# LMX2592.net
KiCad netlist of a schematic drawn in Altium Designer
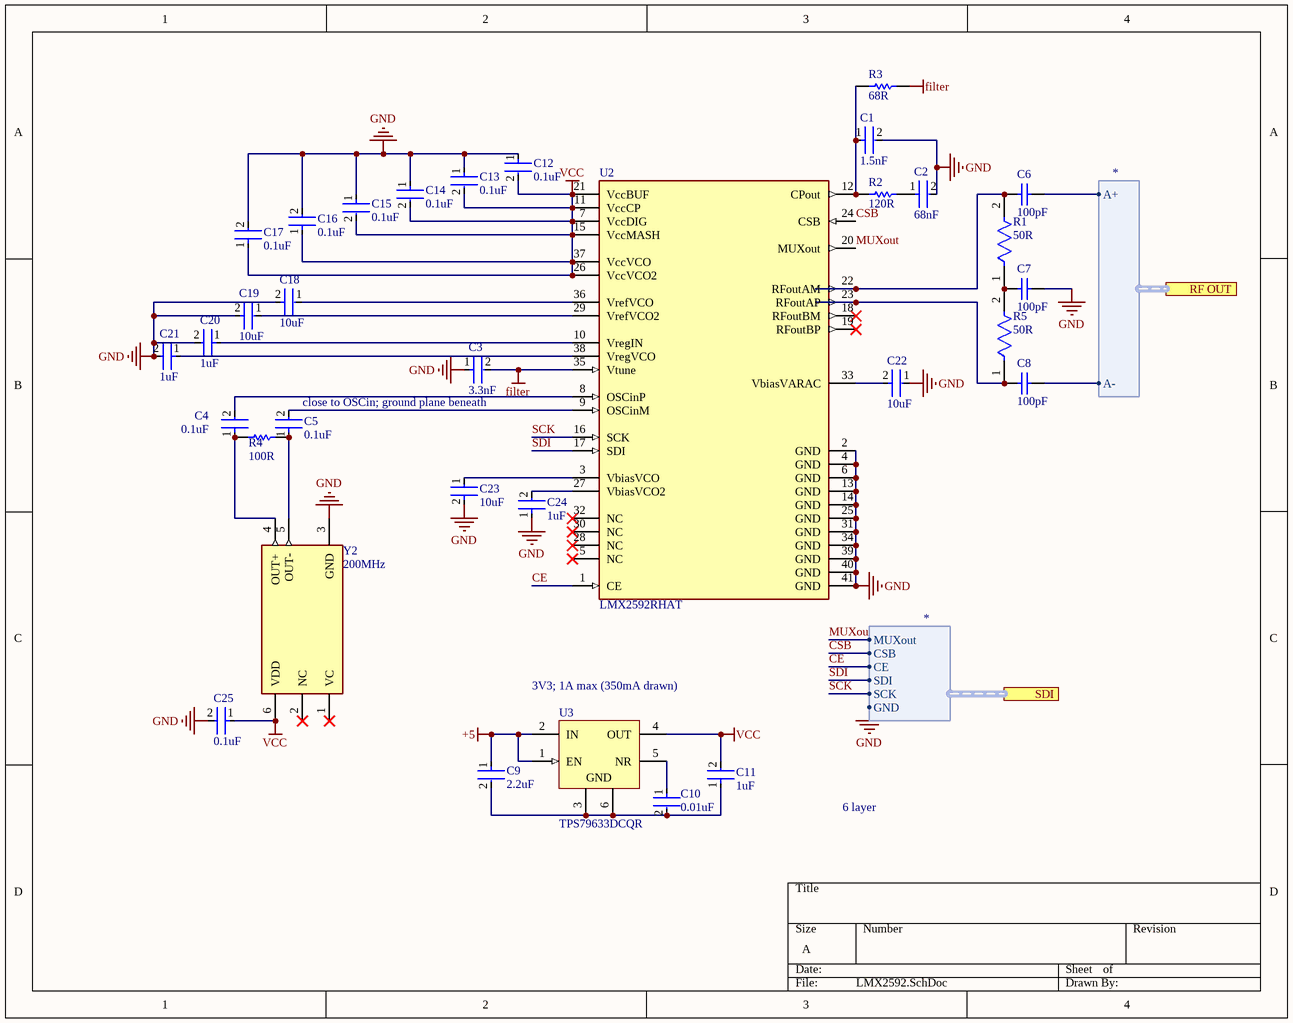
[diagram p0: LMX2592.SchDoc]

(export (version "E")
  (design (tool "Eeschema 10.0.6"))
  (components
    (comp (ref "C1")
      (value "1.5nF")
      (footprint "FP-GRM188-0_1-e0_2_0_5-IPC_B")
      (description "Chip Multilayer Ceramic Capacitors for General Purpose, 0603, 1500pF, C0G, 30ppm/°C, 5%, 50V")
      (fields (field (name "TOLERANCE") "5%") (field (name "VOLTAGE") "50V"))
      (libsource (lib "Altium Content Vault") (part "11868f565c42a9108669ba33697ecf6"))
    )
    (comp (ref "C2")
      (value "68nF")
      (footprint "FP-GRM319-0_15-MFG")
      (description "Chip Multilayer Ceramic Capacitors for General Purpose, 1206, 68000pF, C0G, 30ppm/°C, 5%, 50V")
      (libsource (lib "Altium Content Vault") (part "b4654b650e69147ec39a6b967a45e02"))
    )
    (comp (ref "C3")
      (value "3.3nF")
      (footprint "FP-GCM188-0_1-MFG")
      (description "Ceramic Capacitor for Automotive 3.3nF  ±1% 50VDC C0G 0603 Paper T/R")
      (libsource (lib "Altium Content Vault") (part "02cd4be3c70576c341d710602a673aa"))
    )
    (comp (ref "C4")
      (value "0.1uF")
      (footprint "FP-C0603C-CF-MFG")
      (description "CAP CER 0.1UF 50V X7R 0603")
      (fields (field (name "TOLERANCE") "0.1") (field (name "MANUFACTURER") "KEMET"))
      (libsource (lib "Altium Content Vault") (part "b4654b650e69147ec39a6b967a45e02"))
    )
    (comp (ref "C5")
      (value "0.1uF")
      (footprint "FP-C0603C-CF-MFG")
      (description "CAP CER 0.1UF 50V X7R 0603")
      (fields (field (name "TOLERANCE") "0.1") (field (name "MANUFACTURER") "KEMET"))
      (libsource (lib "Altium Content Vault") (part "b4654b650e69147ec39a6b967a45e02"))
    )
    (comp (ref "C6")
      (value "100pF")
      (footprint "CAPC1608X90X35NL10T15")
      (fields (field (name "PART NUMBER") "GRM1885C1H101JA01D") (field (name "MANUFACTURER") "Murata"))
      (libsource (lib "Altium Content Vault") (part "CAP"))
    )
    (comp (ref "C7")
      (value "100pF")
      (footprint "CAPC1608X90X35NL10T15")
      (fields (field (name "PART NUMBER") "GRM1885C1H101JA01D") (field (name "MANUFACTURER") "Murata"))
      (libsource (lib "Altium Content Vault") (part "CAP"))
    )
    (comp (ref "C8")
      (value "100pF")
      (footprint "CAPC1608X90X35NL10T15")
      (fields (field (name "PART NUMBER") "GRM1885C1H101JA01D") (field (name "MANUFACTURER") "Murata"))
      (libsource (lib "Altium Content Vault") (part "CAP"))
    )
    (comp (ref "C9")
      (value "2.2uF")
      (footprint "FP-GRM188-0_1-e0_2_0_5-MFG")
      (description "Chip Multilayer Ceramic Capacitors for General Purpose, 0603, 2.2uF, X7R, 15%, 10%, 10V")
      (fields (field (name "VOLTAGE") "10V") (field (name "TOLERANCE") "10%"))
      (libsource (lib "Altium Content Vault") (part "11868f565c42a9108669ba33697ecf6"))
    )
    (comp (ref "C10")
      (value "0.01uF")
      (footprint "FP-C0603C-CF-MFG")
      (description "CAP CER 10000PF 50V X7R 0603")
      (fields
        (field (name "MANUFACTURER") "KEMET")
        (field (name "OCTOPART") "https://octopart.com/c0603c103k5ractu-kemet-133094")
      )
      (libsource (lib "Altium Content Vault") (part "b4654b650e69147ec39a6b967a45e02"))
    )
    (comp (ref "C11")
      (value "1uF")
      (footprint "FP-0603-L_1_6_0_15-W_0_8-IPC_C")
      (description "Ceramic Capacitor General Use 1uF ±10% 50V X7R 0603")
      (fields (field (name "TOLERANCE") "10%"))
      (libsource (lib "Altium Content Vault") (part "11868f565c42a9108669ba33697ecf6"))
    )
    (comp (ref "C12")
      (value "0.1uF")
      (footprint "FP-C0603C-CF-MFG")
      (description "CAP CER 0.1UF 50V X7R 0603")
      (fields (field (name "TOLERANCE") "0.1") (field (name "MANUFACTURER") "KEMET"))
      (libsource (lib "Altium Content Vault") (part "b4654b650e69147ec39a6b967a45e02"))
    )
    (comp (ref "C13")
      (value "0.1uF")
      (footprint "FP-C0603C-CF-MFG")
      (description "CAP CER 0.1UF 50V X7R 0603")
      (fields (field (name "TOLERANCE") "0.1") (field (name "MANUFACTURER") "KEMET"))
      (libsource (lib "Altium Content Vault") (part "b4654b650e69147ec39a6b967a45e02"))
    )
    (comp (ref "C14")
      (value "0.1uF")
      (footprint "FP-C0603C-CF-MFG")
      (description "CAP CER 0.1UF 50V X7R 0603")
      (fields (field (name "TOLERANCE") "0.1") (field (name "MANUFACTURER") "KEMET"))
      (libsource (lib "Altium Content Vault") (part "b4654b650e69147ec39a6b967a45e02"))
    )
    (comp (ref "C15")
      (value "0.1uF")
      (footprint "FP-C0603C-CF-MFG")
      (description "CAP CER 0.1UF 50V X7R 0603")
      (fields (field (name "TOLERANCE") "0.1") (field (name "MANUFACTURER") "KEMET"))
      (libsource (lib "Altium Content Vault") (part "b4654b650e69147ec39a6b967a45e02"))
    )
    (comp (ref "C16")
      (value "0.1uF")
      (footprint "FP-C0603C-CF-MFG")
      (description "CAP CER 0.1UF 50V X7R 0603")
      (fields (field (name "TOLERANCE") "0.1") (field (name "MANUFACTURER") "KEMET"))
      (libsource (lib "Altium Content Vault") (part "b4654b650e69147ec39a6b967a45e02"))
    )
    (comp (ref "C17")
      (value "0.1uF")
      (footprint "FP-C0603C-CF-MFG")
      (description "CAP CER 0.1UF 50V X7R 0603")
      (fields (field (name "TOLERANCE") "0.1") (field (name "MANUFACTURER") "KEMET"))
      (libsource (lib "Altium Content Vault") (part "b4654b650e69147ec39a6b967a45e02"))
    )
    (comp (ref "C18")
      (value "10uF")
      (footprint "FP-CL21B106KOQNNNE-MFG")
      (description "CAP CER 10UF 16V X7R 0805")
      (fields
        (field (name "MANUFACTURER PART NUMBER") "CL21B106KOQNNNE")
        (field (name "OCTOPART") "https://octopart.com/cl21b106koqnnne-samsung-19832289")
      )
      (libsource (lib "Altium Content Vault") (part "236180d848d6139a670b325ea6854c9"))
    )
    (comp (ref "C19")
      (value "10uF")
      (footprint "FP-CL21B106KOQNNNE-MFG")
      (description "CAP CER 10UF 16V X7R 0805")
      (fields
        (field (name "MANUFACTURER PART NUMBER") "CL21B106KOQNNNE")
        (field (name "OCTOPART") "https://octopart.com/cl21b106koqnnne-samsung-19832289")
      )
      (libsource (lib "Altium Content Vault") (part "236180d848d6139a670b325ea6854c9"))
    )
    (comp (ref "C20")
      (value "1uF")
      (footprint "FP-0603-L_1_6_0_15-W_0_8-IPC_C")
      (description "Ceramic Capacitor General Use 1uF ±10% 50V X7R 0603")
      (fields (field (name "TOLERANCE") "10%"))
      (libsource (lib "Altium Content Vault") (part "11868f565c42a9108669ba33697ecf6"))
    )
    (comp (ref "C21")
      (value "1uF")
      (footprint "FP-0603-L_1_6_0_15-W_0_8-IPC_C")
      (description "Ceramic Capacitor General Use 1uF ±10% 50V X7R 0603")
      (fields (field (name "TOLERANCE") "10%"))
      (libsource (lib "Altium Content Vault") (part "11868f565c42a9108669ba33697ecf6"))
    )
    (comp (ref "C22")
      (value "10uF")
      (footprint "FP-CL21B106KOQNNNE-MFG")
      (description "CAP CER 10UF 16V X7R 0805")
      (fields
        (field (name "MANUFACTURER PART NUMBER") "CL21B106KOQNNNE")
        (field (name "OCTOPART") "https://octopart.com/cl21b106koqnnne-samsung-19832289")
      )
      (libsource (lib "Altium Content Vault") (part "236180d848d6139a670b325ea6854c9"))
    )
    (comp (ref "C23")
      (value "10uF")
      (footprint "FP-CL21B106KOQNNNE-MFG")
      (description "CAP CER 10UF 16V X7R 0805")
      (fields
        (field (name "MANUFACTURER PART NUMBER") "CL21B106KOQNNNE")
        (field (name "OCTOPART") "https://octopart.com/cl21b106koqnnne-samsung-19832289")
      )
      (libsource (lib "Altium Content Vault") (part "236180d848d6139a670b325ea6854c9"))
    )
    (comp (ref "C24")
      (value "1uF")
      (footprint "FP-0603-L_1_6_0_15-W_0_8-IPC_C")
      (description "Ceramic Capacitor General Use 1uF ±10% 50V X7R 0603")
      (fields (field (name "TOLERANCE") "10%"))
      (libsource (lib "Altium Content Vault") (part "11868f565c42a9108669ba33697ecf6"))
    )
    (comp (ref "C25")
      (value "0.1uF")
      (footprint "FP-C0603C-CF-MFG")
      (description "CAP CER 0.1UF 50V X7R 0603")
      (fields (field (name "TOLERANCE") "0.1") (field (name "MANUFACTURER") "KEMET"))
      (libsource (lib "Altium Content Vault") (part "b4654b650e69147ec39a6b967a45e02"))
    )
    (comp (ref "R1")
      (value "50R")
      (footprint "FP-CRCW0603-e3-MFG")
      (description "RES Thick Film, 50Ω, 1%, 0.1W, 100ppm/°C, 0603")
      (fields (field (name "TOLERANCE") "1%"))
      (libsource (lib "Altium Content Vault") (part "1029c3af85768c4190bb7ad29bc67b5"))
    )
    (comp (ref "R2")
      (value "120R")
      (footprint "RESC1608X55X25NL10T15")
      (description "Chip Resistor, 120 Ohm, +/- 1%, 100 mW, -55 to 155 degC, 0603 (1608 Metric), RoHS, Tape and Reel")
      (libsource (lib "Altium Content Vault") (part "RES-2"))
    )
    (comp (ref "R3")
      (value "68R")
      (footprint "RESC1608X55X30ML15T15")
      (fields (field (name "PART NUMBER") "ERJ-3GEYJ680V") (field (name "MANUFACTURER") "Panasonic"))
      (libsource (lib "Altium Content Vault") (part "RES"))
    )
    (comp (ref "R4")
      (value "100R")
      (footprint "RESC1609X50X30ML8T20")
      (description "Chip Resistor, 100 Ohm, +/- 1%, 100 mW,-55 to 155 degC, 0603 (1608 Metric), RoHS, Tape and Ree")
      (fields (field (name "MANUFACTURER") "Vishay Semiconductor"))
      (libsource (lib "Altium Content Vault") (part "RES-2"))
    )
    (comp (ref "R5")
      (value "50R")
      (footprint "FP-CRCW0603-e3-MFG")
      (description "RES Thick Film, 50Ω, 1%, 0.1W, 100ppm/°C, 0603")
      (fields (field (name "TOLERANCE") "1%"))
      (libsource (lib "Altium Content Vault") (part "1029c3af85768c4190bb7ad29bc67b5"))
    )
    (comp (ref "U2")
      (value "LMX2592RHAT")
      (footprint "FP-RHA0040H-IPC_B")
      (description "IC PLL FREQ SYNTH W/VCO 40VQFN")
      (libsource (lib "Altium Content Vault") (part "9e82714c564c87cee1c1c12d4cd209e"))
    )
    (comp (ref "U3")
      (value "TPS79633DCQR")
      (footprint "DCQ0006A_L")
      (fields (field (name "MANUFACTURER") "Texas Instruments"))
      (libsource (lib "Altium Content Vault") (part "TI-TPS7XXXXXXXX"))
    )
    (comp (ref "Y2")
      (value "200MHz")
      (footprint "FP-SiT5021AI-MFG")
      (description "MEMS OSC VCTCXO 200.0000MHZ LVDS")
      (libsource (lib "Altium Content Vault") (part "a0ff00efb61d16d854f6ec510733f8b"))
    )
  )
  (nets
    (net (code "2") (name "+5") (class "Default")
      (node (ref "C9") (pin "1") (pinfunction "1_1") (pintype "passive"))
      (node (ref "U3") (pin "1") (pinfunction "EN_1") (pintype "input"))
      (node (ref "U3") (pin "2") (pinfunction "IN_2") (pintype "power_in"))
    )
    (net (code "3") (name "/A+") (class "Default")
      (node (ref "C6") (pin "2") (pinfunction "2_2") (pintype "passive"))
    )
    (net (code "4") (name "/A-") (class "Default")
      (node (ref "C8") (pin "2") (pinfunction "2_2") (pintype "passive"))
    )
    (net (code "5") (name "/CE") (class "Default")
      (node (ref "U2") (pin "1") (pinfunction "CE_1") (pintype "input"))
    )
    (net (code "6") (name "/CSB") (class "Default")
      (node (ref "U2") (pin "24") (pinfunction "CSB_24") (pintype "input"))
    )
    (net (code "7") (name "/MUXout") (class "Default")
      (node (ref "U2") (pin "20") (pinfunction "MUXout_20") (pintype "output"))
    )
    (net (code "8") (name "/SCK") (class "Default")
      (node (ref "U2") (pin "16") (pinfunction "SCK_16") (pintype "input"))
    )
    (net (code "9") (name "/SDI") (class "Default")
      (node (ref "U2") (pin "17") (pinfunction "SDI_17") (pintype "input"))
    )
    (net (code "11") (name "GND") (class "Default")
      (node (ref "C1") (pin "2") (pinfunction "2_2") (pintype "passive"))
      (node (ref "C12") (pin "1") (pinfunction "1_1") (pintype "passive"))
      (node (ref "C13") (pin "1") (pinfunction "1_1") (pintype "passive"))
      (node (ref "C14") (pin "1") (pinfunction "1_1") (pintype "passive"))
      (node (ref "C15") (pin "1") (pinfunction "1_1") (pintype "passive"))
      (node (ref "C16") (pin "2") (pinfunction "2_2") (pintype "passive"))
      (node (ref "C17") (pin "2") (pinfunction "2_2") (pintype "passive"))
      (node (ref "C18") (pin "2") (pinfunction "2_2") (pintype "passive"))
      (node (ref "C19") (pin "2") (pinfunction "2_2") (pintype "passive"))
      (node (ref "C2") (pin "2") (pinfunction "2_2") (pintype "passive"))
      (node (ref "C20") (pin "2") (pinfunction "2_2") (pintype "passive"))
      (node (ref "C21") (pin "2") (pinfunction "2_2") (pintype "passive"))
      (node (ref "C22") (pin "1") (pinfunction "1_1") (pintype "passive"))
      (node (ref "C23") (pin "2") (pinfunction "2_2") (pintype "passive"))
      (node (ref "C24") (pin "1") (pinfunction "1_1") (pintype "passive"))
      (node (ref "C25") (pin "2") (pinfunction "2_2") (pintype "passive"))
      (node (ref "C3") (pin "1") (pinfunction "1_1") (pintype "passive"))
      (node (ref "C7") (pin "2") (pinfunction "2_2") (pintype "passive"))
      (node (ref "U2") (pin "13") (pinfunction "GND_13") (pintype "power_in"))
      (node (ref "U2") (pin "14") (pinfunction "GND_14") (pintype "power_in"))
      (node (ref "U2") (pin "2") (pinfunction "GND_2") (pintype "power_in"))
      (node (ref "U2") (pin "25") (pinfunction "GND_25") (pintype "power_in"))
      (node (ref "U2") (pin "31") (pinfunction "GND_31") (pintype "power_in"))
      (node (ref "U2") (pin "34") (pinfunction "GND_34") (pintype "power_in"))
      (node (ref "U2") (pin "39") (pinfunction "GND_39") (pintype "power_in"))
      (node (ref "U2") (pin "4") (pinfunction "GND_4") (pintype "power_in"))
      (node (ref "U2") (pin "40") (pinfunction "GND_40") (pintype "power_in"))
      (node (ref "U2") (pin "41") (pinfunction "GND_41") (pintype "power_in"))
      (node (ref "U2") (pin "6") (pinfunction "GND_6") (pintype "power_in"))
      (node (ref "Y2") (pin "3") (pinfunction "GND_3") (pintype "power_in"))
    )
    (net (code "12") (name "Net-(C2-Pad1)") (class "Default")
      (node (ref "C2") (pin "1") (pinfunction "1_1") (pintype "passive"))
      (node (ref "R2") (pin "2") (pinfunction "2_2") (pintype "passive"))
    )
    (net (code "13") (name "Net-(C7-Pad1)") (class "Default")
      (node (ref "C7") (pin "1") (pinfunction "1_1") (pintype "passive"))
      (node (ref "R1") (pin "1") (pinfunction "1_1") (pintype "passive"))
      (node (ref "R5") (pin "2") (pinfunction "2_2") (pintype "passive"))
    )
    (net (code "14") (name "Net-(C10-Pad2)") (class "Default")
      (node (ref "C10") (pin "2") (pinfunction "2_2") (pintype "passive"))
      (node (ref "C11") (pin "1") (pinfunction "1_1") (pintype "passive"))
      (node (ref "C9") (pin "2") (pinfunction "2_2") (pintype "passive"))
      (node (ref "U3") (pin "3") (pinfunction "GND_3") (pintype "power_in"))
      (node (ref "U3") (pin "6") (pinfunction "GND_6") (pintype "power_in"))
    )
    (net (code "15") (name "Net-(U2-CPout)") (class "Default")
      (node (ref "C1") (pin "1") (pinfunction "1_1") (pintype "passive"))
      (node (ref "R2") (pin "1") (pinfunction "1_1") (pintype "passive"))
      (node (ref "R3") (pin "1") (pinfunction "1_1") (pintype "passive"))
      (node (ref "U2") (pin "12") (pinfunction "CPout_12") (pintype "output"))
    )
    (net (code "16") (name "Net-(U2-OSCinM)") (class "Default")
      (node (ref "C5") (pin "2") (pinfunction "2_2") (pintype "passive"))
      (node (ref "U2") (pin "9") (pinfunction "OSCinM_9") (pintype "input"))
    )
    (net (code "17") (name "Net-(U2-OSCinP)") (class "Default")
      (node (ref "C4") (pin "2") (pinfunction "2_2") (pintype "passive"))
      (node (ref "U2") (pin "8") (pinfunction "OSCinP_8") (pintype "input"))
    )
    (net (code "18") (name "Net-(U2-RFoutAM)") (class "Default")
      (node (ref "C6") (pin "1") (pinfunction "1_1") (pintype "passive"))
      (node (ref "R1") (pin "2") (pinfunction "2_2") (pintype "passive"))
      (node (ref "U2") (pin "22") (pinfunction "RFoutAM_22") (pintype "output"))
    )
    (net (code "19") (name "Net-(U2-RFoutAP)") (class "Default")
      (node (ref "C8") (pin "1") (pinfunction "1_1") (pintype "passive"))
      (node (ref "R5") (pin "1") (pinfunction "1_1") (pintype "passive"))
      (node (ref "U2") (pin "23") (pinfunction "RFoutAP_23") (pintype "output"))
    )
    (net (code "20") (name "Net-(U2-VbiasVARAC)") (class "Default")
      (node (ref "C22") (pin "2") (pinfunction "2_2") (pintype "passive"))
      (node (ref "U2") (pin "33") (pinfunction "VbiasVARAC_33") (pintype "passive"))
    )
    (net (code "21") (name "Net-(U2-VbiasVCO)") (class "Default")
      (node (ref "C23") (pin "1") (pinfunction "1_1") (pintype "passive"))
      (node (ref "U2") (pin "3") (pinfunction "VbiasVCO_3") (pintype "passive"))
    )
    (net (code "22") (name "Net-(U2-VbiasVCO2)") (class "Default")
      (node (ref "C24") (pin "2") (pinfunction "2_2") (pintype "passive"))
      (node (ref "U2") (pin "27") (pinfunction "VbiasVCO2_27") (pintype "passive"))
    )
    (net (code "23") (name "Net-(U2-VrefVCO)") (class "Default")
      (node (ref "C18") (pin "1") (pinfunction "1_1") (pintype "passive"))
      (node (ref "U2") (pin "36") (pinfunction "VrefVCO_36") (pintype "passive"))
    )
    (net (code "24") (name "Net-(U2-VrefVCO2)") (class "Default")
      (node (ref "C19") (pin "1") (pinfunction "1_1") (pintype "passive"))
      (node (ref "U2") (pin "29") (pinfunction "VrefVCO2_29") (pintype "passive"))
    )
    (net (code "25") (name "Net-(U2-VregIN)") (class "Default")
      (node (ref "C20") (pin "1") (pinfunction "1_1") (pintype "passive"))
      (node (ref "U2") (pin "10") (pinfunction "VregIN_10") (pintype "passive"))
    )
    (net (code "26") (name "Net-(U2-VregVCO)") (class "Default")
      (node (ref "C21") (pin "1") (pinfunction "1_1") (pintype "passive"))
      (node (ref "U2") (pin "38") (pinfunction "VregVCO_38") (pintype "passive"))
    )
    (net (code "27") (name "Net-(U3-NR)") (class "Default")
      (node (ref "C10") (pin "1") (pinfunction "1_1") (pintype "passive"))
      (node (ref "U3") (pin "5") (pinfunction "NR_5") (pintype "passive"))
    )
    (net (code "28") (name "Net-(Y2-OUT+)") (class "Default")
      (node (ref "C4") (pin "1") (pinfunction "1_1") (pintype "passive"))
      (node (ref "R4") (pin "1") (pinfunction "1_1") (pintype "passive"))
      (node (ref "Y2") (pin "4") (pinfunction "OUT+_4") (pintype "output"))
    )
    (net (code "29") (name "Net-(Y2-OUT-)") (class "Default")
      (node (ref "C5") (pin "1") (pinfunction "1_1") (pintype "passive"))
      (node (ref "R4") (pin "2") (pinfunction "2_2") (pintype "passive"))
      (node (ref "Y2") (pin "5") (pinfunction "OUT-_5") (pintype "output"))
    )
    (net (code "30") (name "VCC") (class "Default")
      (node (ref "C11") (pin "2") (pinfunction "2_2") (pintype "passive"))
      (node (ref "C12") (pin "2") (pinfunction "2_2") (pintype "passive"))
      (node (ref "C13") (pin "2") (pinfunction "2_2") (pintype "passive"))
      (node (ref "C14") (pin "2") (pinfunction "2_2") (pintype "passive"))
      (node (ref "C15") (pin "2") (pinfunction "2_2") (pintype "passive"))
      (node (ref "C16") (pin "1") (pinfunction "1_1") (pintype "passive"))
      (node (ref "C17") (pin "1") (pinfunction "1_1") (pintype "passive"))
      (node (ref "C25") (pin "1") (pinfunction "1_1") (pintype "passive"))
      (node (ref "U2") (pin "11") (pinfunction "VccCP_11") (pintype "power_in"))
      (node (ref "U2") (pin "15") (pinfunction "VccMASH_15") (pintype "power_in"))
      (node (ref "U2") (pin "21") (pinfunction "VccBUF_21") (pintype "power_in"))
      (node (ref "U2") (pin "26") (pinfunction "VccVCO2_26") (pintype "power_in"))
      (node (ref "U2") (pin "37") (pinfunction "VccVCO_37") (pintype "passive"))
      (node (ref "U2") (pin "7") (pinfunction "VccDIG_7") (pintype "power_in"))
      (node (ref "U3") (pin "4") (pinfunction "OUT_4") (pintype "power_in"))
      (node (ref "Y2") (pin "6") (pinfunction "VDD_6") (pintype "power_in"))
    )
    (net (code "31") (name "filter") (class "Default")
      (node (ref "C3") (pin "2") (pinfunction "2_2") (pintype "passive"))
      (node (ref "R3") (pin "2") (pinfunction "2_2") (pintype "passive"))
      (node (ref "U2") (pin "35") (pinfunction "Vtune_35") (pintype "input"))
    )
    (net (code "32") (name "unconnected-(U2-NC-Pad5)") (class "Default")
      (node (ref "U2") (pin "5") (pinfunction "NC_5") (pintype "passive+no_connect"))
    )
    (net (code "33") (name "unconnected-(U2-NC-Pad28)") (class "Default")
      (node (ref "U2") (pin "28") (pinfunction "NC_28") (pintype "passive+no_connect"))
    )
    (net (code "34") (name "unconnected-(U2-NC-Pad30)") (class "Default")
      (node (ref "U2") (pin "30") (pinfunction "NC_30") (pintype "passive+no_connect"))
    )
    (net (code "35") (name "unconnected-(U2-NC-Pad32)") (class "Default")
      (node (ref "U2") (pin "32") (pinfunction "NC_32") (pintype "passive+no_connect"))
    )
    (net (code "36") (name "unconnected-(U2-RFoutBM-Pad18)") (class "Default")
      (node (ref "U2") (pin "18") (pinfunction "RFoutBM_18") (pintype "output+no_connect"))
    )
    (net (code "37") (name "unconnected-(U2-RFoutBP-Pad19)") (class "Default")
      (node (ref "U2") (pin "19") (pinfunction "RFoutBP_19") (pintype "output+no_connect"))
    )
    (net (code "38") (name "unconnected-(Y2-NC-Pad2)") (class "Default")
      (node (ref "Y2") (pin "2") (pinfunction "NC_2") (pintype "passive+no_connect"))
    )
    (net (code "39") (name "unconnected-(Y2-VC-Pad1)") (class "Default")
      (node (ref "Y2") (pin "1") (pinfunction "VC_1") (pintype "passive+no_connect"))
    )
  )
)
